# projeto_jcarlos_compacta.net
KiCad netlist of a schematic drawn in EAGLE
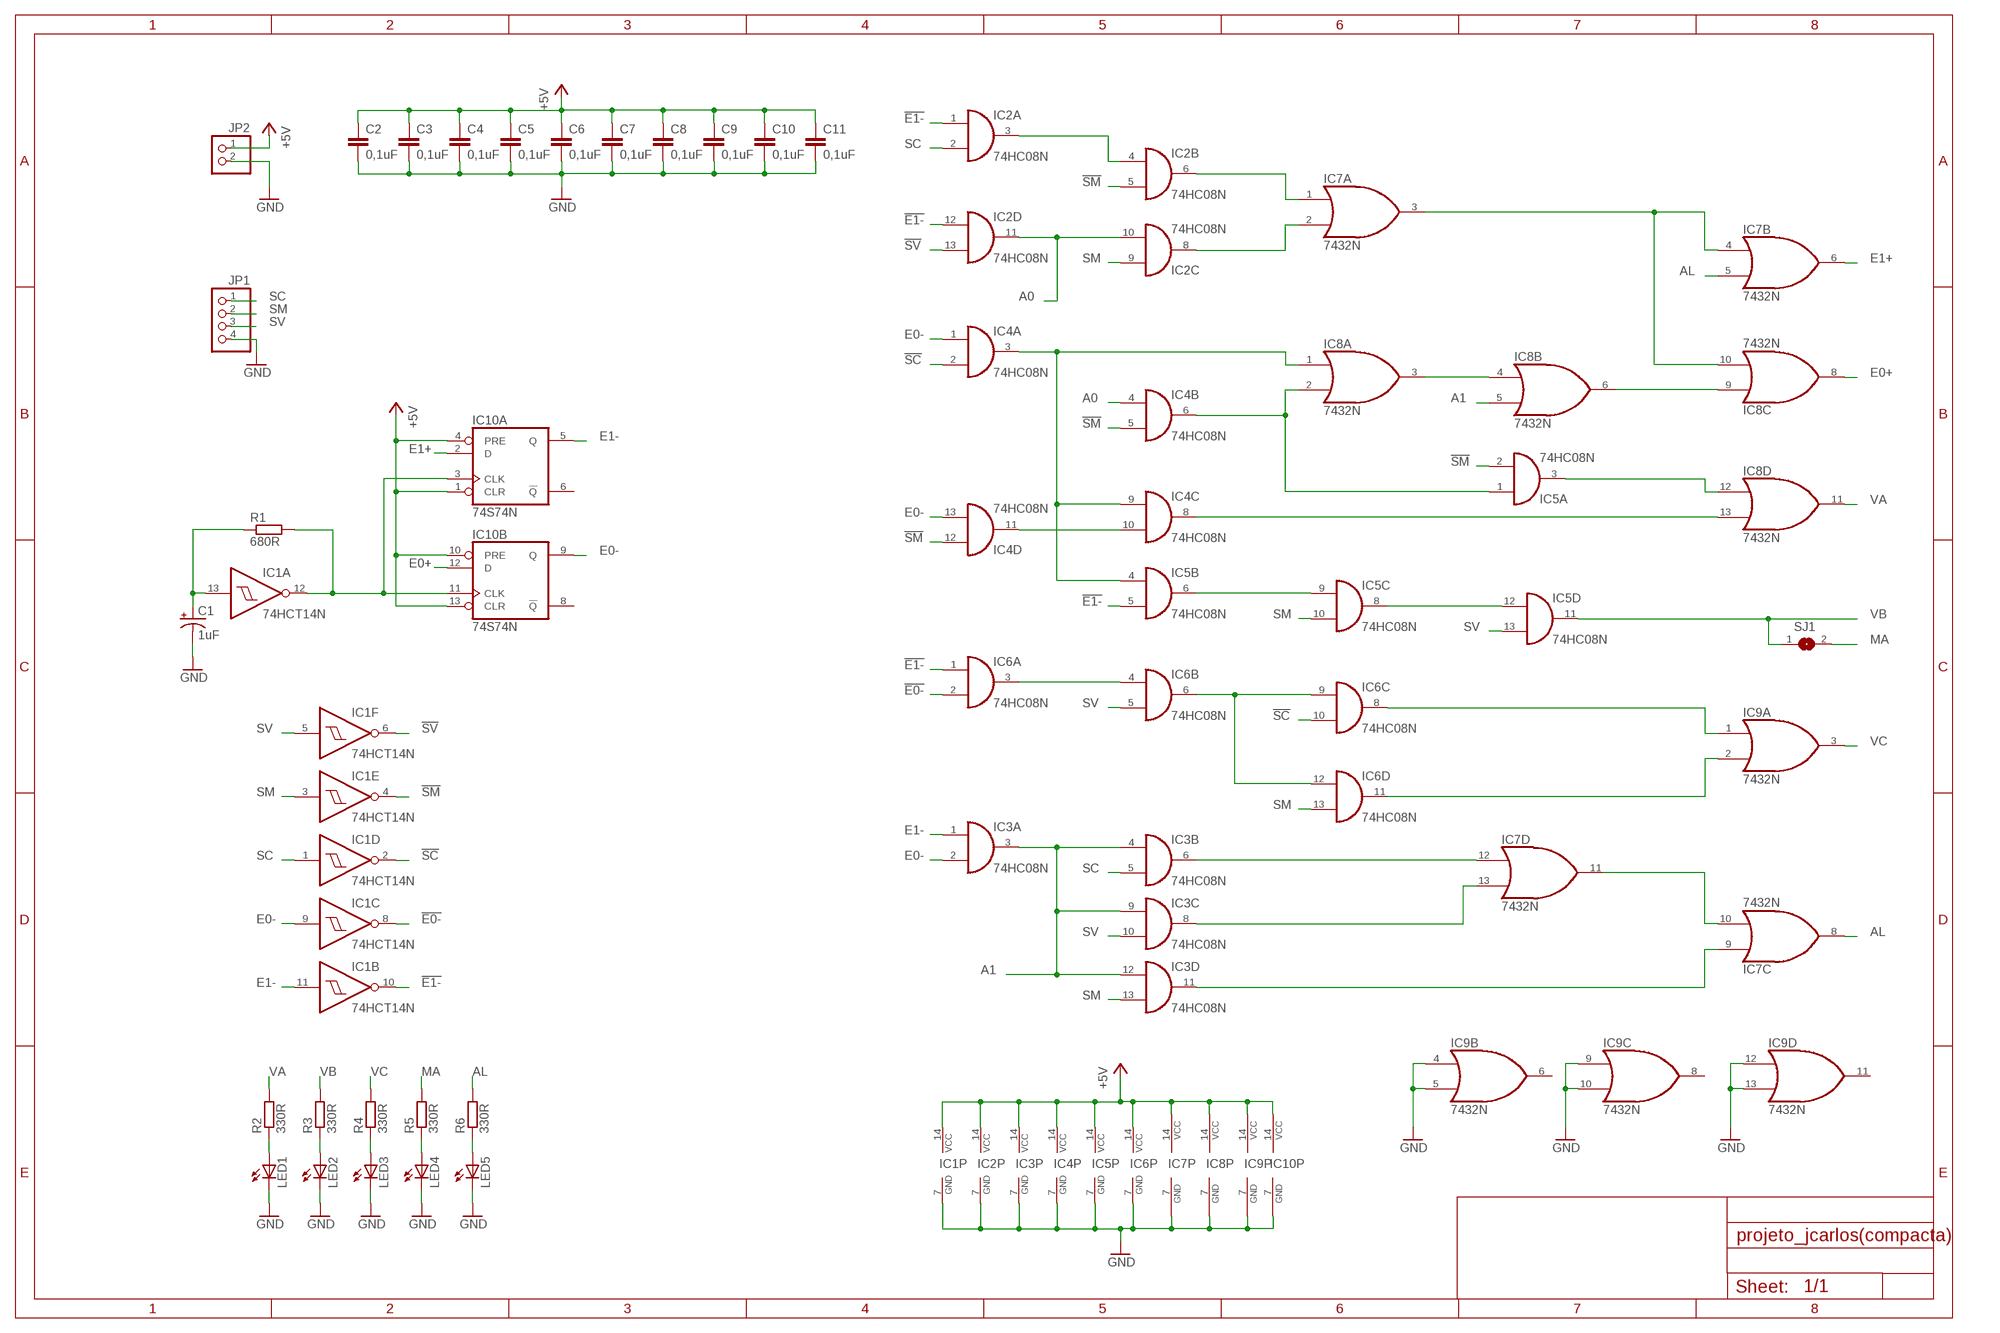
[diagram p0: schematic, sheet 1]

(export (version "E")
  (design (tool "Eeschema 10.0.6"))
  (components
    (comp (ref "C1")
      (value "1uF")
      (footprint "eagle-import:E5-6")
      (libsource (lib "eagle-import") (part "CPOL-USE5-6"))
    )
    (comp (ref "C2")
      (value "0,1uF")
      (footprint "eagle-import:C025-025X050")
      (libsource (lib "eagle-import") (part "C-EU025-025X050"))
    )
    (comp (ref "C3")
      (value "0,1uF")
      (footprint "eagle-import:C025-025X050")
      (libsource (lib "eagle-import") (part "C-EU025-025X050"))
    )
    (comp (ref "C4")
      (value "0,1uF")
      (footprint "eagle-import:C025-025X050")
      (libsource (lib "eagle-import") (part "C-EU025-025X050"))
    )
    (comp (ref "C5")
      (value "0,1uF")
      (footprint "eagle-import:C025-025X050")
      (libsource (lib "eagle-import") (part "C-EU025-025X050"))
    )
    (comp (ref "C6")
      (value "0,1uF")
      (footprint "eagle-import:C025-025X050")
      (libsource (lib "eagle-import") (part "C-EU025-025X050"))
    )
    (comp (ref "C7")
      (value "0,1uF")
      (footprint "eagle-import:C025-025X050")
      (libsource (lib "eagle-import") (part "C-EU025-025X050"))
    )
    (comp (ref "C8")
      (value "0,1uF")
      (footprint "eagle-import:C025-025X050")
      (libsource (lib "eagle-import") (part "C-EU025-025X050"))
    )
    (comp (ref "C9")
      (value "0,1uF")
      (footprint "eagle-import:C025-025X050")
      (libsource (lib "eagle-import") (part "C-EU025-025X050"))
    )
    (comp (ref "C10")
      (value "0,1uF")
      (footprint "eagle-import:C025-025X050")
      (libsource (lib "eagle-import") (part "C-EU025-025X050"))
    )
    (comp (ref "C11")
      (value "0,1uF")
      (footprint "eagle-import:C025-025X050")
      (libsource (lib "eagle-import") (part "C-EU025-025X050"))
    )
    (comp (ref "IC1")
      (value "74HCT14N")
      (footprint "eagle-import:DIL14")
      (libsource (lib "eagle-import") (part "7414NHCT"))
    )
    (comp (ref "IC2")
      (value "74HC08N")
      (footprint "eagle-import:DIL14")
      (libsource (lib "eagle-import") (part "7408NHC"))
    )
    (comp (ref "IC3")
      (value "74HC08N")
      (footprint "eagle-import:DIL14")
      (libsource (lib "eagle-import") (part "7408NHC"))
    )
    (comp (ref "IC4")
      (value "74HC08N")
      (footprint "eagle-import:DIL14")
      (libsource (lib "eagle-import") (part "7408NHC"))
    )
    (comp (ref "IC5")
      (value "74HC08N")
      (footprint "eagle-import:DIL14")
      (libsource (lib "eagle-import") (part "7408NHC"))
    )
    (comp (ref "IC6")
      (value "74HC08N")
      (footprint "eagle-import:DIL14")
      (libsource (lib "eagle-import") (part "7408NHC"))
    )
    (comp (ref "IC7")
      (value "7432N")
      (footprint "eagle-import:DIL14")
      (libsource (lib "eagle-import") (part "7432N"))
    )
    (comp (ref "IC8")
      (value "7432N")
      (footprint "eagle-import:DIL14")
      (libsource (lib "eagle-import") (part "7432N"))
    )
    (comp (ref "IC9")
      (value "7432N")
      (footprint "eagle-import:DIL14")
      (libsource (lib "eagle-import") (part "7432N"))
    )
    (comp (ref "IC10")
      (value "74S74N")
      (footprint "eagle-import:DIL14")
      (libsource (lib "eagle-import") (part "7474NS"))
    )
    (comp (ref "JP1")
      (value "PINHD-1X4")
      (footprint "eagle-import:1X04")
      (libsource (lib "eagle-import") (part "PINHD-1X4"))
    )
    (comp (ref "JP2")
      (value "PINHD-1X2")
      (footprint "eagle-import:1X02")
      (libsource (lib "eagle-import") (part "PINHD-1X2"))
    )
    (comp (ref "LED1")
      (value "LED5MM")
      (footprint "eagle-import:LED5MM")
      (libsource (lib "eagle-import") (part "LED5MM"))
    )
    (comp (ref "LED2")
      (value "LED5MM")
      (footprint "eagle-import:LED5MM")
      (libsource (lib "eagle-import") (part "LED5MM"))
    )
    (comp (ref "LED3")
      (value "LED5MM")
      (footprint "eagle-import:LED5MM")
      (libsource (lib "eagle-import") (part "LED5MM"))
    )
    (comp (ref "LED4")
      (value "LED5MM")
      (footprint "eagle-import:LED5MM")
      (libsource (lib "eagle-import") (part "LED5MM"))
    )
    (comp (ref "LED5")
      (value "LED5MM")
      (footprint "eagle-import:LED5MM")
      (libsource (lib "eagle-import") (part "LED5MM"))
    )
    (comp (ref "R1")
      (value "680R")
      (footprint "eagle-import:0204_5")
      (libsource (lib "eagle-import") (part "R-EU_0204/5"))
    )
    (comp (ref "R2")
      (value "330R")
      (footprint "eagle-import:0204_5")
      (libsource (lib "eagle-import") (part "R-EU_0204/5"))
    )
    (comp (ref "R3")
      (value "330R")
      (footprint "eagle-import:0204_5")
      (libsource (lib "eagle-import") (part "R-EU_0204/5"))
    )
    (comp (ref "R4")
      (value "330R")
      (footprint "eagle-import:0204_5")
      (libsource (lib "eagle-import") (part "R-EU_0204/5"))
    )
    (comp (ref "R5")
      (value "330R")
      (footprint "eagle-import:0204_5")
      (libsource (lib "eagle-import") (part "R-EU_0204/5"))
    )
    (comp (ref "R6")
      (value "330R")
      (footprint "eagle-import:0204_5")
      (libsource (lib "eagle-import") (part "R-EU_0204/5"))
    )
    (comp (ref "SJ1") (value "SJ") (footprint "eagle-import:SJ") (libsource (lib "eagle-import") (part "SJ")))
  )
  (nets
    (net (code "1") (name "+5V") (class "Default")
      (node (ref "C10") (pin "1") (pinfunction "1_1") (pintype "passive"))
      (node (ref "C11") (pin "1") (pinfunction "1_1") (pintype "passive"))
      (node (ref "C2") (pin "1") (pinfunction "1_1") (pintype "passive"))
      (node (ref "C3") (pin "1") (pinfunction "1_1") (pintype "passive"))
      (node (ref "C4") (pin "1") (pinfunction "1_1") (pintype "passive"))
      (node (ref "C5") (pin "1") (pinfunction "1_1") (pintype "passive"))
      (node (ref "C6") (pin "1") (pinfunction "1_1") (pintype "passive"))
      (node (ref "C7") (pin "1") (pinfunction "1_1") (pintype "passive"))
      (node (ref "C8") (pin "1") (pinfunction "1_1") (pintype "passive"))
      (node (ref "C9") (pin "1") (pinfunction "1_1") (pintype "passive"))
      (node (ref "IC1") (pin "14") (pinfunction "VCC_14") (pintype "power_in"))
      (node (ref "IC10") (pin "1") (pinfunction "CLR_1") (pintype "input"))
      (node (ref "IC10") (pin "10") (pinfunction "PRE_10") (pintype "input"))
      (node (ref "IC10") (pin "13") (pinfunction "CLR_13") (pintype "input"))
      (node (ref "IC10") (pin "14") (pinfunction "VCC_14") (pintype "power_in"))
      (node (ref "IC10") (pin "4") (pinfunction "PRE_4") (pintype "input"))
      (node (ref "IC2") (pin "14") (pinfunction "VCC_14") (pintype "power_in"))
      (node (ref "IC3") (pin "14") (pinfunction "VCC_14") (pintype "power_in"))
      (node (ref "IC4") (pin "14") (pinfunction "VCC_14") (pintype "power_in"))
      (node (ref "IC5") (pin "14") (pinfunction "VCC_14") (pintype "power_in"))
      (node (ref "IC6") (pin "14") (pinfunction "VCC_14") (pintype "power_in"))
      (node (ref "IC7") (pin "14") (pinfunction "VCC_14") (pintype "power_in"))
      (node (ref "IC8") (pin "14") (pinfunction "VCC_14") (pintype "power_in"))
      (node (ref "IC9") (pin "14") (pinfunction "VCC_14") (pintype "power_in"))
      (node (ref "JP2") (pin "1") (pinfunction "1_1") (pintype "passive"))
    )
    (net (code "2") (name "/A0") (class "Default")
      (node (ref "IC2") (pin "10") (pinfunction "I1_10") (pintype "input"))
      (node (ref "IC2") (pin "11") (pinfunction "O_11") (pintype "output"))
      (node (ref "IC4") (pin "4") (pinfunction "I0_4") (pintype "input"))
    )
    (net (code "3") (name "/A1") (class "Default")
      (node (ref "IC3") (pin "12") (pinfunction "I0_12") (pintype "input"))
      (node (ref "IC3") (pin "3") (pinfunction "O_3") (pintype "output"))
      (node (ref "IC3") (pin "4") (pinfunction "I0_4") (pintype "input"))
      (node (ref "IC3") (pin "9") (pinfunction "I0_9") (pintype "input"))
      (node (ref "IC8") (pin "5") (pinfunction "I1_5") (pintype "input"))
    )
    (net (code "4") (name "/AL") (class "Default")
      (node (ref "IC7") (pin "5") (pinfunction "I1_5") (pintype "input"))
      (node (ref "IC7") (pin "8") (pinfunction "O_8") (pintype "output"))
      (node (ref "R6") (pin "2") (pinfunction "2_2") (pintype "passive"))
    )
    (net (code "5") (name "/E0+") (class "Default")
      (node (ref "IC10") (pin "12") (pinfunction "D_12") (pintype "input"))
      (node (ref "IC8") (pin "8") (pinfunction "O_8") (pintype "output"))
    )
    (net (code "6") (name "/E0-") (class "Default")
      (node (ref "IC1") (pin "9") (pinfunction "I_9") (pintype "input"))
      (node (ref "IC10") (pin "9") (pinfunction "Q_9") (pintype "output"))
      (node (ref "IC3") (pin "2") (pinfunction "I1_2") (pintype "input"))
      (node (ref "IC4") (pin "1") (pinfunction "I0_1") (pintype "input"))
      (node (ref "IC4") (pin "13") (pinfunction "I1_13") (pintype "input"))
    )
    (net (code "7") (name "/E1+") (class "Default")
      (node (ref "IC10") (pin "2") (pinfunction "D_2") (pintype "input"))
      (node (ref "IC7") (pin "6") (pinfunction "O_6") (pintype "output"))
    )
    (net (code "8") (name "/E1-") (class "Default")
      (node (ref "IC1") (pin "11") (pinfunction "I_11") (pintype "input"))
      (node (ref "IC10") (pin "5") (pinfunction "Q_5") (pintype "output"))
      (node (ref "IC3") (pin "1") (pinfunction "I0_1") (pintype "input"))
    )
    (net (code "9") (name "/MA") (class "Default")
      (node (ref "R5") (pin "2") (pinfunction "2_2") (pintype "passive"))
      (node (ref "SJ1") (pin "2") (pinfunction "2_2") (pintype "passive"))
    )
    (net (code "10") (name "/SC") (class "Default")
      (node (ref "IC1") (pin "1") (pinfunction "I_1") (pintype "input"))
      (node (ref "IC2") (pin "2") (pinfunction "I1_2") (pintype "input"))
      (node (ref "IC3") (pin "5") (pinfunction "I1_5") (pintype "input"))
      (node (ref "JP1") (pin "1") (pinfunction "1_1") (pintype "passive"))
    )
    (net (code "11") (name "/SM") (class "Default")
      (node (ref "IC1") (pin "3") (pinfunction "I_3") (pintype "input"))
      (node (ref "IC2") (pin "9") (pinfunction "I0_9") (pintype "input"))
      (node (ref "IC3") (pin "13") (pinfunction "I1_13") (pintype "input"))
      (node (ref "IC5") (pin "10") (pinfunction "I1_10") (pintype "input"))
      (node (ref "IC6") (pin "13") (pinfunction "I1_13") (pintype "input"))
      (node (ref "JP1") (pin "2") (pinfunction "2_2") (pintype "passive"))
    )
    (net (code "12") (name "/SV") (class "Default")
      (node (ref "IC1") (pin "5") (pinfunction "I_5") (pintype "input"))
      (node (ref "IC3") (pin "10") (pinfunction "I1_10") (pintype "input"))
      (node (ref "IC5") (pin "13") (pinfunction "I1_13") (pintype "input"))
      (node (ref "IC6") (pin "5") (pinfunction "I1_5") (pintype "input"))
      (node (ref "JP1") (pin "3") (pinfunction "3_3") (pintype "passive"))
    )
    (net (code "13") (name "/VA") (class "Default")
      (node (ref "IC8") (pin "11") (pinfunction "O_11") (pintype "output"))
      (node (ref "R2") (pin "2") (pinfunction "2_2") (pintype "passive"))
    )
    (net (code "14") (name "/VB") (class "Default")
      (node (ref "IC5") (pin "11") (pinfunction "O_11") (pintype "output"))
      (node (ref "R3") (pin "2") (pinfunction "2_2") (pintype "passive"))
      (node (ref "SJ1") (pin "1") (pinfunction "1_1") (pintype "passive"))
    )
    (net (code "15") (name "/VC") (class "Default")
      (node (ref "IC9") (pin "3") (pinfunction "O_3") (pintype "output"))
      (node (ref "R4") (pin "2") (pinfunction "2_2") (pintype "passive"))
    )
    (net (code "16") (name "/~{E0-}") (class "Default")
      (node (ref "IC1") (pin "8") (pinfunction "O_8") (pintype "output"))
      (node (ref "IC6") (pin "2") (pinfunction "I1_2") (pintype "input"))
    )
    (net (code "17") (name "/~{E1-}") (class "Default")
      (node (ref "IC1") (pin "10") (pinfunction "O_10") (pintype "output"))
      (node (ref "IC2") (pin "1") (pinfunction "I0_1") (pintype "input"))
      (node (ref "IC2") (pin "12") (pinfunction "I0_12") (pintype "input"))
      (node (ref "IC5") (pin "5") (pinfunction "I1_5") (pintype "input"))
      (node (ref "IC6") (pin "1") (pinfunction "I0_1") (pintype "input"))
    )
    (net (code "18") (name "/~{SC}") (class "Default")
      (node (ref "IC1") (pin "2") (pinfunction "O_2") (pintype "output"))
      (node (ref "IC4") (pin "2") (pinfunction "I1_2") (pintype "input"))
      (node (ref "IC6") (pin "10") (pinfunction "I1_10") (pintype "input"))
    )
    (net (code "19") (name "/~{SM}") (class "Default")
      (node (ref "IC1") (pin "4") (pinfunction "O_4") (pintype "output"))
      (node (ref "IC2") (pin "5") (pinfunction "I1_5") (pintype "input"))
      (node (ref "IC4") (pin "12") (pinfunction "I0_12") (pintype "input"))
      (node (ref "IC4") (pin "5") (pinfunction "I1_5") (pintype "input"))
      (node (ref "IC5") (pin "2") (pinfunction "I1_2") (pintype "input"))
    )
    (net (code "20") (name "/~{SV}") (class "Default")
      (node (ref "IC1") (pin "6") (pinfunction "O_6") (pintype "output"))
      (node (ref "IC2") (pin "13") (pinfunction "I1_13") (pintype "input"))
    )
    (net (code "21") (name "GND") (class "Default")
      (node (ref "C1") (pin "-") (pinfunction "-_-") (pintype "passive"))
      (node (ref "C10") (pin "2") (pinfunction "2_2") (pintype "passive"))
      (node (ref "C11") (pin "2") (pinfunction "2_2") (pintype "passive"))
      (node (ref "C2") (pin "2") (pinfunction "2_2") (pintype "passive"))
      (node (ref "C3") (pin "2") (pinfunction "2_2") (pintype "passive"))
      (node (ref "C4") (pin "2") (pinfunction "2_2") (pintype "passive"))
      (node (ref "C5") (pin "2") (pinfunction "2_2") (pintype "passive"))
      (node (ref "C6") (pin "2") (pinfunction "2_2") (pintype "passive"))
      (node (ref "C7") (pin "2") (pinfunction "2_2") (pintype "passive"))
      (node (ref "C8") (pin "2") (pinfunction "2_2") (pintype "passive"))
      (node (ref "C9") (pin "2") (pinfunction "2_2") (pintype "passive"))
      (node (ref "IC1") (pin "7") (pinfunction "GND_7") (pintype "power_in"))
      (node (ref "IC10") (pin "7") (pinfunction "GND_7") (pintype "power_in"))
      (node (ref "IC2") (pin "7") (pinfunction "GND_7") (pintype "power_in"))
      (node (ref "IC3") (pin "7") (pinfunction "GND_7") (pintype "power_in"))
      (node (ref "IC4") (pin "7") (pinfunction "GND_7") (pintype "power_in"))
      (node (ref "IC5") (pin "7") (pinfunction "GND_7") (pintype "power_in"))
      (node (ref "IC6") (pin "7") (pinfunction "GND_7") (pintype "power_in"))
      (node (ref "IC7") (pin "7") (pinfunction "GND_7") (pintype "power_in"))
      (node (ref "IC8") (pin "7") (pinfunction "GND_7") (pintype "power_in"))
      (node (ref "IC9") (pin "10") (pinfunction "I1_10") (pintype "input"))
      (node (ref "IC9") (pin "12") (pinfunction "I0_12") (pintype "input"))
      (node (ref "IC9") (pin "13") (pinfunction "I1_13") (pintype "input"))
      (node (ref "IC9") (pin "4") (pinfunction "I0_4") (pintype "input"))
      (node (ref "IC9") (pin "5") (pinfunction "I1_5") (pintype "input"))
      (node (ref "IC9") (pin "7") (pinfunction "GND_7") (pintype "power_in"))
      (node (ref "IC9") (pin "9") (pinfunction "I0_9") (pintype "input"))
      (node (ref "JP1") (pin "4") (pinfunction "4_4") (pintype "passive"))
      (node (ref "JP2") (pin "2") (pinfunction "2_2") (pintype "passive"))
      (node (ref "LED1") (pin "K") (pinfunction "C_K") (pintype "passive"))
      (node (ref "LED2") (pin "K") (pinfunction "C_K") (pintype "passive"))
      (node (ref "LED3") (pin "K") (pinfunction "C_K") (pintype "passive"))
      (node (ref "LED4") (pin "K") (pinfunction "C_K") (pintype "passive"))
      (node (ref "LED5") (pin "K") (pinfunction "C_K") (pintype "passive"))
    )
    (net (code "22") (name "Net-(IC1A-I)") (class "Default")
      (node (ref "C1") (pin "+") (pinfunction "+_+") (pintype "passive"))
      (node (ref "IC1") (pin "13") (pinfunction "I_13") (pintype "input"))
      (node (ref "R1") (pin "1") (pinfunction "1_1") (pintype "passive"))
    )
    (net (code "23") (name "Net-(IC2A-O)") (class "Default")
      (node (ref "IC2") (pin "3") (pinfunction "O_3") (pintype "output"))
      (node (ref "IC2") (pin "4") (pinfunction "I0_4") (pintype "input"))
    )
    (net (code "24") (name "Net-(IC2B-O)") (class "Default")
      (node (ref "IC2") (pin "6") (pinfunction "O_6") (pintype "output"))
      (node (ref "IC7") (pin "1") (pinfunction "I0_1") (pintype "input"))
    )
    (net (code "25") (name "Net-(IC2C-O)") (class "Default")
      (node (ref "IC2") (pin "8") (pinfunction "O_8") (pintype "output"))
      (node (ref "IC7") (pin "2") (pinfunction "I1_2") (pintype "input"))
    )
    (net (code "26") (name "Net-(IC3B-O)") (class "Default")
      (node (ref "IC3") (pin "6") (pinfunction "O_6") (pintype "output"))
      (node (ref "IC7") (pin "12") (pinfunction "I0_12") (pintype "input"))
    )
    (net (code "27") (name "Net-(IC3C-O)") (class "Default")
      (node (ref "IC3") (pin "8") (pinfunction "O_8") (pintype "output"))
      (node (ref "IC7") (pin "13") (pinfunction "I1_13") (pintype "input"))
    )
    (net (code "28") (name "Net-(IC3D-O)") (class "Default")
      (node (ref "IC3") (pin "11") (pinfunction "O_11") (pintype "output"))
      (node (ref "IC7") (pin "9") (pinfunction "I0_9") (pintype "input"))
    )
    (net (code "29") (name "Net-(IC4A-O)") (class "Default")
      (node (ref "IC4") (pin "3") (pinfunction "O_3") (pintype "output"))
      (node (ref "IC4") (pin "9") (pinfunction "I0_9") (pintype "input"))
      (node (ref "IC5") (pin "4") (pinfunction "I0_4") (pintype "input"))
      (node (ref "IC8") (pin "1") (pinfunction "I0_1") (pintype "input"))
    )
    (net (code "30") (name "Net-(IC4B-O)") (class "Default")
      (node (ref "IC4") (pin "6") (pinfunction "O_6") (pintype "output"))
      (node (ref "IC5") (pin "1") (pinfunction "I0_1") (pintype "input"))
      (node (ref "IC8") (pin "2") (pinfunction "I1_2") (pintype "input"))
    )
    (net (code "31") (name "Net-(IC4C-I1)") (class "Default")
      (node (ref "IC4") (pin "10") (pinfunction "I1_10") (pintype "input"))
      (node (ref "IC4") (pin "11") (pinfunction "O_11") (pintype "output"))
    )
    (net (code "32") (name "Net-(IC4C-O)") (class "Default")
      (node (ref "IC4") (pin "8") (pinfunction "O_8") (pintype "output"))
      (node (ref "IC8") (pin "13") (pinfunction "I1_13") (pintype "input"))
    )
    (net (code "33") (name "Net-(IC5A-O)") (class "Default")
      (node (ref "IC5") (pin "3") (pinfunction "O_3") (pintype "output"))
      (node (ref "IC8") (pin "12") (pinfunction "I0_12") (pintype "input"))
    )
    (net (code "34") (name "Net-(IC5B-O)") (class "Default")
      (node (ref "IC5") (pin "6") (pinfunction "O_6") (pintype "output"))
      (node (ref "IC5") (pin "9") (pinfunction "I0_9") (pintype "input"))
    )
    (net (code "35") (name "Net-(IC5C-O)") (class "Default")
      (node (ref "IC5") (pin "12") (pinfunction "I0_12") (pintype "input"))
      (node (ref "IC5") (pin "8") (pinfunction "O_8") (pintype "output"))
    )
    (net (code "36") (name "Net-(IC6A-O)") (class "Default")
      (node (ref "IC6") (pin "3") (pinfunction "O_3") (pintype "output"))
      (node (ref "IC6") (pin "4") (pinfunction "I0_4") (pintype "input"))
    )
    (net (code "37") (name "Net-(IC6B-O)") (class "Default")
      (node (ref "IC6") (pin "12") (pinfunction "I0_12") (pintype "input"))
      (node (ref "IC6") (pin "6") (pinfunction "O_6") (pintype "output"))
      (node (ref "IC6") (pin "9") (pinfunction "I0_9") (pintype "input"))
    )
    (net (code "38") (name "Net-(IC6C-O)") (class "Default")
      (node (ref "IC6") (pin "8") (pinfunction "O_8") (pintype "output"))
      (node (ref "IC9") (pin "1") (pinfunction "I0_1") (pintype "input"))
    )
    (net (code "39") (name "Net-(IC6D-O)") (class "Default")
      (node (ref "IC6") (pin "11") (pinfunction "O_11") (pintype "output"))
      (node (ref "IC9") (pin "2") (pinfunction "I1_2") (pintype "input"))
    )
    (net (code "40") (name "Net-(IC7A-O)") (class "Default")
      (node (ref "IC7") (pin "3") (pinfunction "O_3") (pintype "output"))
      (node (ref "IC7") (pin "4") (pinfunction "I0_4") (pintype "input"))
      (node (ref "IC8") (pin "10") (pinfunction "I1_10") (pintype "input"))
    )
    (net (code "41") (name "Net-(IC7C-I1)") (class "Default")
      (node (ref "IC7") (pin "10") (pinfunction "I1_10") (pintype "input"))
      (node (ref "IC7") (pin "11") (pinfunction "O_11") (pintype "output"))
    )
    (net (code "42") (name "Net-(IC8A-O)") (class "Default")
      (node (ref "IC8") (pin "3") (pinfunction "O_3") (pintype "output"))
      (node (ref "IC8") (pin "4") (pinfunction "I0_4") (pintype "input"))
    )
    (net (code "43") (name "Net-(IC8B-O)") (class "Default")
      (node (ref "IC8") (pin "6") (pinfunction "O_6") (pintype "output"))
      (node (ref "IC8") (pin "9") (pinfunction "I0_9") (pintype "input"))
    )
    (net (code "44") (name "Net-(IC10A-CLK)") (class "Default")
      (node (ref "IC1") (pin "12") (pinfunction "O_12") (pintype "output"))
      (node (ref "IC10") (pin "11") (pinfunction "CLK_11") (pintype "input"))
      (node (ref "IC10") (pin "3") (pinfunction "CLK_3") (pintype "input"))
      (node (ref "R1") (pin "2") (pinfunction "2_2") (pintype "passive"))
    )
    (net (code "45") (name "Net-(LED1-PadA)") (class "Default")
      (node (ref "LED1") (pin "A") (pinfunction "A_A") (pintype "passive"))
      (node (ref "R2") (pin "1") (pinfunction "1_1") (pintype "passive"))
    )
    (net (code "46") (name "Net-(LED2-PadA)") (class "Default")
      (node (ref "LED2") (pin "A") (pinfunction "A_A") (pintype "passive"))
      (node (ref "R3") (pin "1") (pinfunction "1_1") (pintype "passive"))
    )
    (net (code "47") (name "Net-(LED3-PadA)") (class "Default")
      (node (ref "LED3") (pin "A") (pinfunction "A_A") (pintype "passive"))
      (node (ref "R4") (pin "1") (pinfunction "1_1") (pintype "passive"))
    )
    (net (code "48") (name "Net-(LED4-PadA)") (class "Default")
      (node (ref "LED4") (pin "A") (pinfunction "A_A") (pintype "passive"))
      (node (ref "R5") (pin "1") (pinfunction "1_1") (pintype "passive"))
    )
    (net (code "49") (name "Net-(LED5-PadA)") (class "Default")
      (node (ref "LED5") (pin "A") (pinfunction "A_A") (pintype "passive"))
      (node (ref "R6") (pin "1") (pinfunction "1_1") (pintype "passive"))
    )
    (net (code "50") (name "unconnected-(IC9B-O-Pad6)") (class "Default")
      (node (ref "IC9") (pin "6") (pinfunction "O_6") (pintype "output"))
    )
    (net (code "51") (name "unconnected-(IC9C-O-Pad8)") (class "Default")
      (node (ref "IC9") (pin "8") (pinfunction "O_8") (pintype "output"))
    )
    (net (code "52") (name "unconnected-(IC9D-O-Pad11)") (class "Default")
      (node (ref "IC9") (pin "11") (pinfunction "O_11") (pintype "output"))
    )
    (net (code "53") (name "unconnected-(IC10A-~{Q}-Pad6)") (class "Default")
      (node (ref "IC10") (pin "6") (pinfunction "~{Q}_6") (pintype "output"))
    )
    (net (code "54") (name "unconnected-(IC10B-~{Q}-Pad8)") (class "Default")
      (node (ref "IC10") (pin "8") (pinfunction "~{Q}_8") (pintype "output"))
    )
  )
)
